# glowbelt.net
KiCad netlist of a schematic drawn in EAGLE
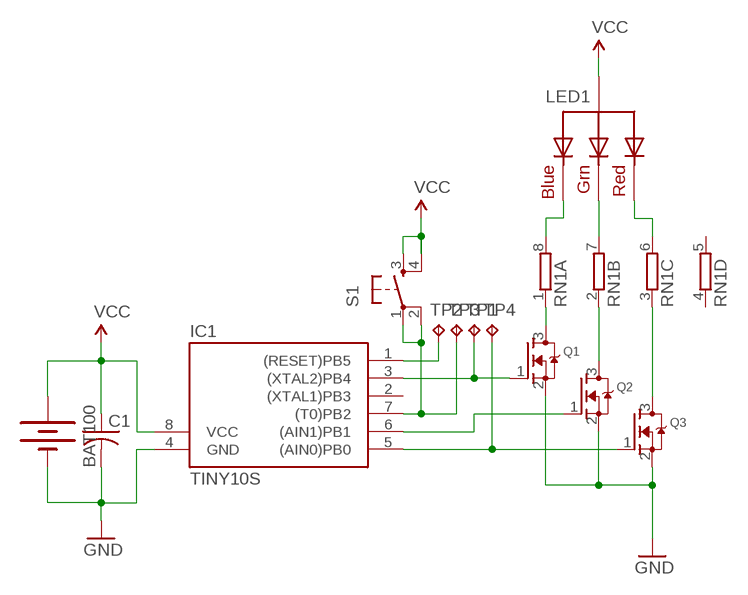
[diagram p0: schematic, sheet 1]

(export (version "E")
  (design (tool "Eeschema 10.0.6"))
  (components
    (comp (ref "BAT100")
      (value "BATTERY20SMD")
      (footprint "eagle-import:BATTCON_20MM")
      (libsource (lib "eagle-import") (part "BATTERY20SMD"))
    )
    (comp (ref "C1")
      (value "C-USC1206")
      (footprint "eagle-import:C1206")
      (libsource (lib "eagle-import") (part "C-USC1206"))
    )
    (comp (ref "IC1")
      (value "TINY10S")
      (footprint "eagle-import:SOIC8")
      (libsource (lib "eagle-import") (part "TINY10S"))
    )
    (comp (ref "LED1")
      (value "RGBLED_CA-5MM")
      (footprint "eagle-import:LED5MMRGB")
      (libsource (lib "eagle-import") (part "RGBLED_CA-5MM"))
    )
    (comp (ref "Q1")
      (value "MOSFET-NREFLOW")
      (footprint "eagle-import:SOT23")
      (libsource (lib "eagle-import") (part "MOSFET-NREFLOW"))
    )
    (comp (ref "Q2")
      (value "MOSFET-NREFLOW")
      (footprint "eagle-import:SOT23")
      (libsource (lib "eagle-import") (part "MOSFET-NREFLOW"))
    )
    (comp (ref "Q3")
      (value "MOSFET-NREFLOW")
      (footprint "eagle-import:SOT23")
      (libsource (lib "eagle-import") (part "MOSFET-NREFLOW"))
    )
    (comp (ref "RN1")
      (value "4R-NEXBS8V")
      (footprint "eagle-import:EXBS8V")
      (libsource (lib "eagle-import") (part "4R-NEXBS8V"))
    )
    (comp (ref "S1")
      (value "TAC_SWITCHSMD")
      (footprint "eagle-import:TACTILE_SWITCH_SMD")
      (libsource (lib "eagle-import") (part "TAC_SWITCHSMD"))
    )
    (comp (ref "TP1")
      (value "TPB1,27")
      (footprint "eagle-import:B1,27")
      (libsource (lib "eagle-import") (part "TPB1,27"))
    )
    (comp (ref "TP2")
      (value "TPB1,27")
      (footprint "eagle-import:B1,27")
      (libsource (lib "eagle-import") (part "TPB1,27"))
    )
    (comp (ref "TP3")
      (value "TPB1,27")
      (footprint "eagle-import:B1,27")
      (libsource (lib "eagle-import") (part "TPB1,27"))
    )
    (comp (ref "TP4")
      (value "TPB1,27")
      (footprint "eagle-import:B1,27")
      (libsource (lib "eagle-import") (part "TPB1,27"))
    )
  )
  (nets
    (net (code "1") (name "GND") (class "Default")
      (node (ref "BAT100") (pin "2") (pinfunction "-_2") (pintype "power_in"))
      (node (ref "C1") (pin "2") (pinfunction "2_2") (pintype "passive"))
      (node (ref "IC1") (pin "4") (pinfunction "GND_4") (pintype "power_in"))
      (node (ref "Q1") (pin "2") (pinfunction "S_2") (pintype "bidirectional"))
      (node (ref "Q2") (pin "2") (pinfunction "S_2") (pintype "bidirectional"))
      (node (ref "Q3") (pin "2") (pinfunction "S_2") (pintype "bidirectional"))
    )
    (net (code "2") (name "Net-(IC1-(AIN0)PB0)") (class "Default")
      (node (ref "IC1") (pin "5") (pinfunction "(AIN0)PB0_5") (pintype "bidirectional"))
      (node (ref "Q3") (pin "1") (pinfunction "G_1") (pintype "bidirectional"))
      (node (ref "TP4") (pin "TP") (pinfunction "TP_TP") (pintype "input"))
    )
    (net (code "3") (name "Net-(IC1-(AIN1)PB1)") (class "Default")
      (node (ref "IC1") (pin "6") (pinfunction "(AIN1)PB1_6") (pintype "bidirectional"))
      (node (ref "Q2") (pin "1") (pinfunction "G_1") (pintype "bidirectional"))
    )
    (net (code "4") (name "Net-(IC1-(RESET)PB5)") (class "Default")
      (node (ref "IC1") (pin "1") (pinfunction "(RESET)PB5_1") (pintype "bidirectional"))
      (node (ref "TP2") (pin "TP") (pinfunction "TP_TP") (pintype "input"))
    )
    (net (code "5") (name "Net-(IC1-(T0)PB2)") (class "Default")
      (node (ref "IC1") (pin "7") (pinfunction "(T0)PB2_7") (pintype "bidirectional"))
      (node (ref "S1") (pin "1") (pinfunction "1_1") (pintype "passive"))
      (node (ref "S1") (pin "2") (pinfunction "2_2") (pintype "passive"))
      (node (ref "TP3") (pin "TP") (pinfunction "TP_TP") (pintype "input"))
    )
    (net (code "6") (name "Net-(IC1-(XTAL2)PB4)") (class "Default")
      (node (ref "IC1") (pin "3") (pinfunction "(XTAL2)PB4_3") (pintype "bidirectional"))
      (node (ref "Q1") (pin "1") (pinfunction "G_1") (pintype "bidirectional"))
      (node (ref "TP1") (pin "TP") (pinfunction "TP_TP") (pintype "input"))
    )
    (net (code "7") (name "Net-(LED1-BLUE)") (class "Default")
      (node (ref "LED1") (pin "4") (pinfunction "BLUE_4") (pintype "bidirectional"))
      (node (ref "RN1") (pin "8") (pinfunction "2_8") (pintype "passive"))
    )
    (net (code "8") (name "Net-(LED1-GREEN)") (class "Default")
      (node (ref "LED1") (pin "3") (pinfunction "GREEN_3") (pintype "bidirectional"))
      (node (ref "RN1") (pin "7") (pinfunction "2_7") (pintype "passive"))
    )
    (net (code "9") (name "Net-(LED1-RED)") (class "Default")
      (node (ref "LED1") (pin "1") (pinfunction "RED_1") (pintype "bidirectional"))
      (node (ref "RN1") (pin "6") (pinfunction "2_6") (pintype "passive"))
    )
    (net (code "10") (name "Net-(Q1-D)") (class "Default")
      (node (ref "Q1") (pin "3") (pinfunction "D_3") (pintype "bidirectional"))
      (node (ref "RN1") (pin "1") (pinfunction "1_1") (pintype "passive"))
    )
    (net (code "11") (name "Net-(Q2-D)") (class "Default")
      (node (ref "Q2") (pin "3") (pinfunction "D_3") (pintype "bidirectional"))
      (node (ref "RN1") (pin "2") (pinfunction "1_2") (pintype "passive"))
    )
    (net (code "12") (name "Net-(Q3-D)") (class "Default")
      (node (ref "Q3") (pin "3") (pinfunction "D_3") (pintype "bidirectional"))
      (node (ref "RN1") (pin "3") (pinfunction "1_3") (pintype "passive"))
    )
    (net (code "13") (name "VCC") (class "Default")
      (node (ref "BAT100") (pin "1") (pinfunction "+_1") (pintype "power_in"))
      (node (ref "C1") (pin "1") (pinfunction "1_1") (pintype "passive"))
      (node (ref "IC1") (pin "8") (pinfunction "VCC_8") (pintype "power_in"))
      (node (ref "LED1") (pin "2") (pinfunction "VCC_2") (pintype "bidirectional"))
      (node (ref "S1") (pin "3") (pinfunction "3_3") (pintype "passive"))
      (node (ref "S1") (pin "4") (pinfunction "4_4") (pintype "passive"))
    )
    (net (code "14") (name "unconnected-(IC1-(XTAL1)PB3-Pad2)") (class "Default")
      (node (ref "IC1") (pin "2") (pinfunction "(XTAL1)PB3_2") (pintype "bidirectional"))
    )
    (net (code "15") (name "unconnected-(RN1D-1-Pad4)") (class "Default")
      (node (ref "RN1") (pin "4") (pinfunction "1_4") (pintype "passive"))
    )
    (net (code "16") (name "unconnected-(RN1D-2-Pad5)") (class "Default")
      (node (ref "RN1") (pin "5") (pinfunction "2_5") (pintype "passive"))
    )
  )
)
